# inout.net
KiCad netlist of a schematic drawn in Altium Designer
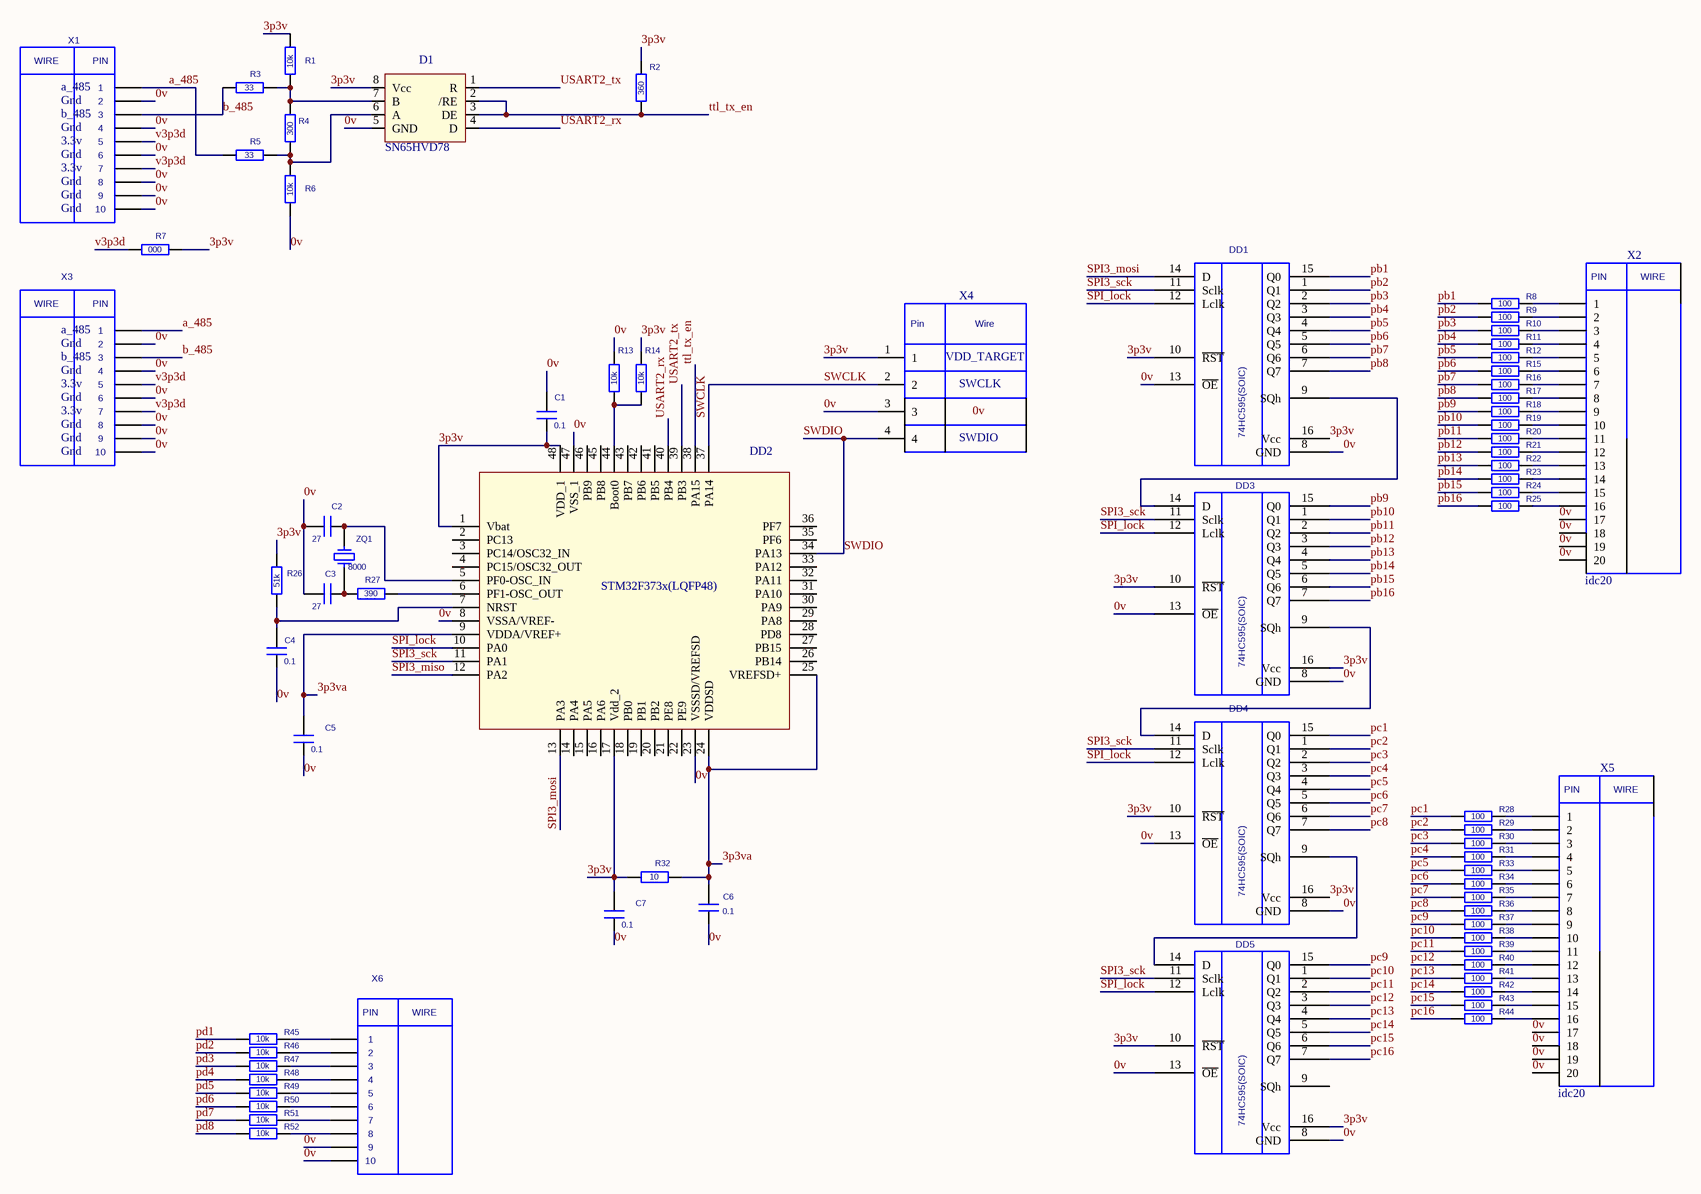
[diagram p0: inout.SchDoc]

(export (version "E")
  (design (tool "Eeschema 10.0.6"))
  (components
    (comp (ref "C1")
      (value "0.1")
      (footprint "CC0805")
      (description "CAP0805")
      (libsource (lib "alexsb") (part "CAP0805"))
    )
    (comp (ref "C2")
      (value "27")
      (footprint "CC0805")
      (description "CAP0805")
      (libsource (lib "alexsb") (part "CAP0805"))
    )
    (comp (ref "C3")
      (value "27")
      (footprint "CC0805")
      (description "CAP0805")
      (libsource (lib "alexsb") (part "CAP0805"))
    )
    (comp (ref "C4")
      (value "0.1")
      (footprint "CC0805")
      (description "CAP0805")
      (libsource (lib "alexsb") (part "CAP0805"))
    )
    (comp (ref "C5")
      (value "0.1")
      (footprint "CC0805")
      (description "CAP0805")
      (libsource (lib "alexsb") (part "CAP0805"))
    )
    (comp (ref "C6")
      (value "0.1")
      (footprint "CC0805")
      (description "CAP0805")
      (libsource (lib "alexsb") (part "CAP0805"))
    )
    (comp (ref "C7")
      (value "0.1")
      (footprint "CC0805")
      (description "CAP0805")
      (libsource (lib "alexsb") (part "CAP0805"))
    )
    (comp (ref "D1") (value "SN65HVD78") (footprint "8S1_M") (libsource (lib "as14120") (part "SN65HVD78")))
    (comp (ref "DD1")
      (value "74HC595(SOIC)")
      (footprint "SO16")
      (libsource (lib "alexsb") (part "74HC595(SOIC)"))
    )
    (comp (ref "DD2")
      (value "STM32F373x(LQFP48)")
      (footprint "LQFP48_L")
      (libsource (lib "alexsb") (part "STM32F373x(LQFP48)"))
    )
    (comp (ref "DD3")
      (value "74HC595(SOIC)")
      (footprint "SO16")
      (libsource (lib "alexsb") (part "74HC595(SOIC)"))
    )
    (comp (ref "DD4")
      (value "74HC595(SOIC)")
      (footprint "SO16")
      (libsource (lib "alexsb") (part "74HC595(SOIC)"))
    )
    (comp (ref "DD5")
      (value "74HC595(SOIC)")
      (footprint "SO16")
      (libsource (lib "alexsb") (part "74HC595(SOIC)"))
    )
    (comp (ref "R1")
      (value "10k")
      (footprint "RC0805")
      (description "RES0805")
      (fields (field (name "Comment") "1K 1% 0805(2012)"))
      (libsource (lib "") (part "RES0805_1"))
    )
    (comp (ref "R2")
      (value "360")
      (footprint "RC0805")
      (description "RES0805")
      (fields (field (name "Comment") "1K 1% 0805(2012)"))
      (libsource (lib "") (part "RES0805_1"))
    )
    (comp (ref "R3")
      (value "33")
      (footprint "RC0805")
      (description "RES0805")
      (fields (field (name "Comment") "1K 1% 0805(2012)"))
      (libsource (lib "") (part "RES0805_1"))
    )
    (comp (ref "R4")
      (value "300")
      (footprint "RC0805")
      (description "RES0805")
      (fields (field (name "Comment") "1K 1% 0805(2012)"))
      (libsource (lib "") (part "RES0805_1"))
    )
    (comp (ref "R5")
      (value "33")
      (footprint "RC0805")
      (description "RES0805")
      (fields (field (name "Comment") "1K 1% 0805(2012)"))
      (libsource (lib "") (part "RES0805_1"))
    )
    (comp (ref "R6")
      (value "10k")
      (footprint "RC0805")
      (description "RES0805")
      (fields (field (name "Comment") "1K 1% 0805(2012)"))
      (libsource (lib "") (part "RES0805_1"))
    )
    (comp (ref "R7")
      (value "000")
      (footprint "RC0805")
      (description "RES0805")
      (fields (field (name "Comment") "1K 1% 0805(2012)"))
      (libsource (lib "") (part "RES0805_1"))
    )
    (comp (ref "R8")
      (value "100")
      (footprint "RC0805")
      (description "RES0805")
      (fields (field (name "Comment") "1K 1% 0805(2012)"))
      (libsource (lib "alexsb") (part "RES0805"))
    )
    (comp (ref "R9")
      (value "100")
      (footprint "RC0805")
      (description "RES0805")
      (fields (field (name "Comment") "1K 1% 0805(2012)"))
      (libsource (lib "alexsb") (part "RES0805"))
    )
    (comp (ref "R10")
      (value "100")
      (footprint "RC0805")
      (description "RES0805")
      (fields (field (name "Comment") "1K 1% 0805(2012)"))
      (libsource (lib "alexsb") (part "RES0805"))
    )
    (comp (ref "R11")
      (value "100")
      (footprint "RC0805")
      (description "RES0805")
      (fields (field (name "Comment") "1K 1% 0805(2012)"))
      (libsource (lib "alexsb") (part "RES0805"))
    )
    (comp (ref "R12")
      (value "100")
      (footprint "RC0805")
      (description "RES0805")
      (fields (field (name "Comment") "1K 1% 0805(2012)"))
      (libsource (lib "alexsb") (part "RES0805"))
    )
    (comp (ref "R13")
      (value "10k")
      (footprint "RC0805")
      (description "RES0805")
      (libsource (lib "") (part "RES0805_1"))
    )
    (comp (ref "R14")
      (value "10k")
      (footprint "RC0805")
      (description "RES0805")
      (libsource (lib "") (part "RES0805_1"))
    )
    (comp (ref "R15")
      (value "100")
      (footprint "RC0805")
      (description "RES0805")
      (fields (field (name "Comment") "1K 1% 0805(2012)"))
      (libsource (lib "alexsb") (part "RES0805"))
    )
    (comp (ref "R16")
      (value "100")
      (footprint "RC0805")
      (description "RES0805")
      (fields (field (name "Comment") "1K 1% 0805(2012)"))
      (libsource (lib "alexsb") (part "RES0805"))
    )
    (comp (ref "R17")
      (value "100")
      (footprint "RC0805")
      (description "RES0805")
      (fields (field (name "Comment") "1K 1% 0805(2012)"))
      (libsource (lib "alexsb") (part "RES0805"))
    )
    (comp (ref "R18")
      (value "100")
      (footprint "RC0805")
      (description "RES0805")
      (fields (field (name "Comment") "1K 1% 0805(2012)"))
      (libsource (lib "alexsb") (part "RES0805"))
    )
    (comp (ref "R19")
      (value "100")
      (footprint "RC0805")
      (description "RES0805")
      (fields (field (name "Comment") "1K 1% 0805(2012)"))
      (libsource (lib "alexsb") (part "RES0805"))
    )
    (comp (ref "R20")
      (value "100")
      (footprint "RC0805")
      (description "RES0805")
      (fields (field (name "Comment") "1K 1% 0805(2012)"))
      (libsource (lib "alexsb") (part "RES0805"))
    )
    (comp (ref "R21")
      (value "100")
      (footprint "RC0805")
      (description "RES0805")
      (fields (field (name "Comment") "1K 1% 0805(2012)"))
      (libsource (lib "alexsb") (part "RES0805"))
    )
    (comp (ref "R22")
      (value "100")
      (footprint "RC0805")
      (description "RES0805")
      (fields (field (name "Comment") "1K 1% 0805(2012)"))
      (libsource (lib "alexsb") (part "RES0805"))
    )
    (comp (ref "R23")
      (value "100")
      (footprint "RC0805")
      (description "RES0805")
      (fields (field (name "Comment") "1K 1% 0805(2012)"))
      (libsource (lib "alexsb") (part "RES0805"))
    )
    (comp (ref "R24")
      (value "100")
      (footprint "RC0805")
      (description "RES0805")
      (fields (field (name "Comment") "1K 1% 0805(2012)"))
      (libsource (lib "alexsb") (part "RES0805"))
    )
    (comp (ref "R25")
      (value "100")
      (footprint "RC0805")
      (description "RES0805")
      (fields (field (name "Comment") "1K 1% 0805(2012)"))
      (libsource (lib "alexsb") (part "RES0805"))
    )
    (comp (ref "R26")
      (value "51k")
      (footprint "RC0805")
      (description "RES0805")
      (libsource (lib "") (part "RES0805_1"))
    )
    (comp (ref "R27")
      (value "390")
      (footprint "RC0805")
      (description "RES0805")
      (libsource (lib "") (part "RES0805_1"))
    )
    (comp (ref "R28")
      (value "100")
      (footprint "RC0805")
      (description "RES0805")
      (fields (field (name "Comment") "1K 1% 0805(2012)"))
      (libsource (lib "alexsb") (part "RES0805"))
    )
    (comp (ref "R29")
      (value "100")
      (footprint "RC0805")
      (description "RES0805")
      (fields (field (name "Comment") "1K 1% 0805(2012)"))
      (libsource (lib "alexsb") (part "RES0805"))
    )
    (comp (ref "R30")
      (value "100")
      (footprint "RC0805")
      (description "RES0805")
      (fields (field (name "Comment") "1K 1% 0805(2012)"))
      (libsource (lib "alexsb") (part "RES0805"))
    )
    (comp (ref "R31")
      (value "100")
      (footprint "RC0805")
      (description "RES0805")
      (fields (field (name "Comment") "1K 1% 0805(2012)"))
      (libsource (lib "alexsb") (part "RES0805"))
    )
    (comp (ref "R32")
      (value "10")
      (footprint "RC0805")
      (description "RES0805")
      (libsource (lib "alexsb") (part "RES0805"))
    )
    (comp (ref "R33")
      (value "100")
      (footprint "RC0805")
      (description "RES0805")
      (fields (field (name "Comment") "1K 1% 0805(2012)"))
      (libsource (lib "alexsb") (part "RES0805"))
    )
    (comp (ref "R34")
      (value "100")
      (footprint "RC0805")
      (description "RES0805")
      (fields (field (name "Comment") "1K 1% 0805(2012)"))
      (libsource (lib "alexsb") (part "RES0805"))
    )
    (comp (ref "R35")
      (value "100")
      (footprint "RC0805")
      (description "RES0805")
      (fields (field (name "Comment") "1K 1% 0805(2012)"))
      (libsource (lib "alexsb") (part "RES0805"))
    )
    (comp (ref "R36")
      (value "100")
      (footprint "RC0805")
      (description "RES0805")
      (fields (field (name "Comment") "1K 1% 0805(2012)"))
      (libsource (lib "alexsb") (part "RES0805"))
    )
    (comp (ref "R37")
      (value "100")
      (footprint "RC0805")
      (description "RES0805")
      (fields (field (name "Comment") "1K 1% 0805(2012)"))
      (libsource (lib "alexsb") (part "RES0805"))
    )
    (comp (ref "R38")
      (value "100")
      (footprint "RC0805")
      (description "RES0805")
      (fields (field (name "Comment") "1K 1% 0805(2012)"))
      (libsource (lib "alexsb") (part "RES0805"))
    )
    (comp (ref "R39")
      (value "100")
      (footprint "RC0805")
      (description "RES0805")
      (fields (field (name "Comment") "1K 1% 0805(2012)"))
      (libsource (lib "alexsb") (part "RES0805"))
    )
    (comp (ref "R40")
      (value "100")
      (footprint "RC0805")
      (description "RES0805")
      (fields (field (name "Comment") "1K 1% 0805(2012)"))
      (libsource (lib "alexsb") (part "RES0805"))
    )
    (comp (ref "R41")
      (value "100")
      (footprint "RC0805")
      (description "RES0805")
      (fields (field (name "Comment") "1K 1% 0805(2012)"))
      (libsource (lib "alexsb") (part "RES0805"))
    )
    (comp (ref "R42")
      (value "100")
      (footprint "RC0805")
      (description "RES0805")
      (fields (field (name "Comment") "1K 1% 0805(2012)"))
      (libsource (lib "alexsb") (part "RES0805"))
    )
    (comp (ref "R43")
      (value "100")
      (footprint "RC0805")
      (description "RES0805")
      (fields (field (name "Comment") "1K 1% 0805(2012)"))
      (libsource (lib "alexsb") (part "RES0805"))
    )
    (comp (ref "R44")
      (value "100")
      (footprint "RC0805")
      (description "RES0805")
      (fields (field (name "Comment") "1K 1% 0805(2012)"))
      (libsource (lib "alexsb") (part "RES0805"))
    )
    (comp (ref "R45")
      (value "10k")
      (footprint "RC0805")
      (description "RES0805")
      (fields (field (name "Comment") "1K 1% 0805(2012)"))
      (libsource (lib "alexsb") (part "RES0805"))
    )
    (comp (ref "R46")
      (value "10k")
      (footprint "RC0805")
      (description "RES0805")
      (fields (field (name "Comment") "1K 1% 0805(2012)"))
      (libsource (lib "alexsb") (part "RES0805"))
    )
    (comp (ref "R47")
      (value "10k")
      (footprint "RC0805")
      (description "RES0805")
      (fields (field (name "Comment") "1K 1% 0805(2012)"))
      (libsource (lib "alexsb") (part "RES0805"))
    )
    (comp (ref "R48")
      (value "10k")
      (footprint "RC0805")
      (description "RES0805")
      (fields (field (name "Comment") "1K 1% 0805(2012)"))
      (libsource (lib "alexsb") (part "RES0805"))
    )
    (comp (ref "R49")
      (value "10k")
      (footprint "RC0805")
      (description "RES0805")
      (fields (field (name "Comment") "1K 1% 0805(2012)"))
      (libsource (lib "alexsb") (part "RES0805"))
    )
    (comp (ref "R50")
      (value "10k")
      (footprint "RC0805")
      (description "RES0805")
      (fields (field (name "Comment") "1K 1% 0805(2012)"))
      (libsource (lib "alexsb") (part "RES0805"))
    )
    (comp (ref "R51")
      (value "10k")
      (footprint "RC0805")
      (description "RES0805")
      (fields (field (name "Comment") "1K 1% 0805(2012)"))
      (libsource (lib "alexsb") (part "RES0805"))
    )
    (comp (ref "R52")
      (value "10k")
      (footprint "RC0805")
      (description "RES0805")
      (fields (field (name "Comment") "1K 1% 0805(2012)"))
      (libsource (lib "alexsb") (part "RES0805"))
    )
    (comp (ref "X1") (value "IDC10") (footprint "IDC10M") (libsource (lib "alexsb") (part "IDC10")))
    (comp (ref "X2") (value "idc20") (footprint "IDC20M") (libsource (lib "alexsb") (part "idc20")))
    (comp (ref "X3") (value "IDC10") (footprint "IDC10M") (libsource (lib "alexsb") (part "IDC10")))
    (comp (ref "X4") (value "*") (footprint "4pin") (libsource (lib "*") (part "4pin")))
    (comp (ref "X5") (value "idc20") (footprint "IDC20M") (libsource (lib "alexsb") (part "idc20")))
    (comp (ref "X6") (value "IDC10") (footprint "IDC10M") (libsource (lib "alexsb") (part "IDC10")))
    (comp (ref "ZQ1")
      (value "8000")
      (footprint "CRYSTAL_Primary")
      (description "REZONATOR")
      (libsource (lib "alexsb") (part "REZONATOR"))
    )
  )
  (nets
    (net (code "1") (name "/0v") (class "Default")
      (node (ref "C1") (pin "2") (pintype "passive"))
      (node (ref "C2") (pin "2") (pintype "passive"))
      (node (ref "C3") (pin "2") (pintype "passive"))
      (node (ref "C4") (pin "1") (pintype "passive"))
      (node (ref "C5") (pin "1") (pintype "passive"))
      (node (ref "C6") (pin "1") (pintype "passive"))
      (node (ref "C7") (pin "1") (pintype "passive"))
      (node (ref "D1") (pin "5") (pinfunction "GND_5") (pintype "passive"))
      (node (ref "DD1") (pin "13") (pinfunction "~{OE}_13") (pintype "passive"))
      (node (ref "DD1") (pin "8") (pinfunction "GND_8") (pintype "passive"))
      (node (ref "DD2") (pin "23") (pinfunction "VSSSD/VREFSD_23") (pintype "passive"))
      (node (ref "DD2") (pin "47") (pinfunction "VSS_1_47") (pintype "passive"))
      (node (ref "DD2") (pin "8") (pinfunction "VSSA/VREF-_8") (pintype "passive"))
      (node (ref "DD3") (pin "13") (pinfunction "~{OE}_13") (pintype "passive"))
      (node (ref "DD3") (pin "8") (pinfunction "GND_8") (pintype "passive"))
      (node (ref "DD4") (pin "13") (pinfunction "~{OE}_13") (pintype "passive"))
      (node (ref "DD4") (pin "8") (pinfunction "GND_8") (pintype "passive"))
      (node (ref "DD5") (pin "13") (pinfunction "~{OE}_13") (pintype "passive"))
      (node (ref "DD5") (pin "8") (pinfunction "GND_8") (pintype "passive"))
      (node (ref "R13") (pin "2") (pintype "passive"))
      (node (ref "R6") (pin "2") (pintype "passive"))
      (node (ref "X1") (pin "10") (pintype "passive"))
      (node (ref "X1") (pin "2") (pintype "passive"))
      (node (ref "X1") (pin "4") (pintype "passive"))
      (node (ref "X1") (pin "6") (pintype "passive"))
      (node (ref "X1") (pin "8") (pintype "passive"))
      (node (ref "X1") (pin "9") (pintype "passive"))
      (node (ref "X2") (pin "17") (pinfunction "17_17") (pintype "passive"))
      (node (ref "X2") (pin "18") (pinfunction "18_18") (pintype "passive"))
      (node (ref "X2") (pin "19") (pinfunction "19_19") (pintype "passive"))
      (node (ref "X2") (pin "20") (pinfunction "20_20") (pintype "passive"))
      (node (ref "X3") (pin "10") (pintype "passive"))
      (node (ref "X3") (pin "2") (pintype "passive"))
      (node (ref "X3") (pin "4") (pintype "passive"))
      (node (ref "X3") (pin "6") (pintype "passive"))
      (node (ref "X3") (pin "8") (pintype "passive"))
      (node (ref "X3") (pin "9") (pintype "passive"))
      (node (ref "X4") (pin "3") (pinfunction "3_3") (pintype "passive"))
      (node (ref "X5") (pin "17") (pinfunction "17_17") (pintype "passive"))
      (node (ref "X5") (pin "18") (pinfunction "18_18") (pintype "passive"))
      (node (ref "X5") (pin "19") (pinfunction "19_19") (pintype "passive"))
      (node (ref "X5") (pin "20") (pinfunction "20_20") (pintype "passive"))
      (node (ref "X6") (pin "10") (pintype "passive"))
      (node (ref "X6") (pin "9") (pintype "passive"))
    )
    (net (code "2") (name "/3p3v") (class "Default")
      (node (ref "C1") (pin "1") (pintype "passive"))
      (node (ref "C7") (pin "2") (pintype "passive"))
      (node (ref "D1") (pin "8") (pinfunction "Vcc_8") (pintype "passive"))
      (node (ref "DD1") (pin "10") (pinfunction "~{RST}_10") (pintype "passive"))
      (node (ref "DD1") (pin "16") (pinfunction "Vcc_16") (pintype "passive"))
      (node (ref "DD2") (pin "1") (pinfunction "Vbat_1") (pintype "passive"))
      (node (ref "DD2") (pin "17") (pinfunction "Vdd_2_17") (pintype "passive"))
      (node (ref "DD2") (pin "48") (pinfunction "VDD_1_48") (pintype "passive"))
      (node (ref "DD3") (pin "10") (pinfunction "~{RST}_10") (pintype "passive"))
      (node (ref "DD3") (pin "16") (pinfunction "Vcc_16") (pintype "passive"))
      (node (ref "DD4") (pin "10") (pinfunction "~{RST}_10") (pintype "passive"))
      (node (ref "DD4") (pin "16") (pinfunction "Vcc_16") (pintype "passive"))
      (node (ref "DD5") (pin "10") (pinfunction "~{RST}_10") (pintype "passive"))
      (node (ref "DD5") (pin "16") (pinfunction "Vcc_16") (pintype "passive"))
      (node (ref "R1") (pin "1") (pintype "passive"))
      (node (ref "R14") (pin "2") (pintype "passive"))
      (node (ref "R2") (pin "1") (pintype "passive"))
      (node (ref "R26") (pin "2") (pintype "passive"))
      (node (ref "R32") (pin "1") (pintype "passive"))
      (node (ref "R7") (pin "2") (pintype "passive"))
      (node (ref "X4") (pin "1") (pinfunction "1_1") (pintype "passive"))
    )
    (net (code "3") (name "/3p3va") (class "Default")
      (node (ref "C5") (pin "2") (pintype "passive"))
      (node (ref "C6") (pin "2") (pintype "passive"))
      (node (ref "DD2") (pin "24") (pinfunction "VDDSD_24") (pintype "passive"))
      (node (ref "DD2") (pin "25") (pinfunction "VREFSD+_25") (pintype "passive"))
      (node (ref "DD2") (pin "9") (pinfunction "VDDA/VREF+_9") (pintype "passive"))
      (node (ref "R32") (pin "2") (pintype "passive"))
    )
    (net (code "4") (name "/SPI3_miso") (class "Default")
      (node (ref "DD2") (pin "12") (pinfunction "PA2_12") (pintype "passive"))
    )
    (net (code "5") (name "/SPI3_mosi") (class "Default")
      (node (ref "DD1") (pin "14") (pinfunction "D_14") (pintype "passive"))
      (node (ref "DD2") (pin "13") (pinfunction "PA3_13") (pintype "passive"))
    )
    (net (code "6") (name "/SPI3_sck") (class "Default")
      (node (ref "DD1") (pin "11") (pinfunction "Sclk_11") (pintype "passive"))
      (node (ref "DD2") (pin "11") (pinfunction "PA1_11") (pintype "passive"))
      (node (ref "DD3") (pin "11") (pinfunction "Sclk_11") (pintype "passive"))
      (node (ref "DD4") (pin "11") (pinfunction "Sclk_11") (pintype "passive"))
      (node (ref "DD5") (pin "11") (pinfunction "Sclk_11") (pintype "passive"))
    )
    (net (code "7") (name "/SPI_lock") (class "Default")
      (node (ref "DD1") (pin "12") (pinfunction "Lclk_12") (pintype "passive"))
      (node (ref "DD2") (pin "10") (pinfunction "PA0_10") (pintype "passive"))
      (node (ref "DD3") (pin "12") (pinfunction "Lclk_12") (pintype "passive"))
      (node (ref "DD4") (pin "12") (pinfunction "Lclk_12") (pintype "passive"))
      (node (ref "DD5") (pin "12") (pinfunction "Lclk_12") (pintype "passive"))
    )
    (net (code "8") (name "/SWCLK") (class "Default")
      (node (ref "DD2") (pin "37") (pinfunction "PA14_37") (pintype "passive"))
      (node (ref "X4") (pin "2") (pinfunction "2_2") (pintype "passive"))
    )
    (net (code "9") (name "/SWDIO") (class "Default")
      (node (ref "DD2") (pin "34") (pinfunction "PA13_34") (pintype "passive"))
      (node (ref "X4") (pin "4") (pinfunction "4_4") (pintype "passive"))
    )
    (net (code "10") (name "/USART2_rx") (class "Default")
      (node (ref "D1") (pin "4") (pinfunction "D_4") (pintype "passive"))
      (node (ref "DD2") (pin "40") (pinfunction "PB4_40") (pintype "passive"))
    )
    (net (code "11") (name "/USART2_tx") (class "Default")
      (node (ref "D1") (pin "1") (pinfunction "R_1") (pintype "passive"))
      (node (ref "DD2") (pin "39") (pinfunction "PB3_39") (pintype "passive"))
    )
    (net (code "12") (name "/a_485") (class "Default")
      (node (ref "R5") (pin "1") (pintype "passive"))
      (node (ref "X1") (pin "1") (pintype "passive"))
      (node (ref "X3") (pin "1") (pintype "passive"))
    )
    (net (code "13") (name "/b_485") (class "Default")
      (node (ref "R3") (pin "1") (pintype "passive"))
      (node (ref "X1") (pin "3") (pintype "passive"))
      (node (ref "X3") (pin "3") (pintype "passive"))
    )
    (net (code "14") (name "/pb1") (class "Default")
      (node (ref "DD1") (pin "15") (pinfunction "Q0_15") (pintype "passive"))
      (node (ref "R8") (pin "2") (pintype "passive"))
    )
    (net (code "15") (name "/pb2") (class "Default")
      (node (ref "DD1") (pin "1") (pinfunction "Q1_1") (pintype "passive"))
      (node (ref "R9") (pin "2") (pintype "passive"))
    )
    (net (code "16") (name "/pb3") (class "Default")
      (node (ref "DD1") (pin "2") (pinfunction "Q2_2") (pintype "passive"))
      (node (ref "R10") (pin "2") (pintype "passive"))
    )
    (net (code "17") (name "/pb4") (class "Default")
      (node (ref "DD1") (pin "3") (pinfunction "Q3_3") (pintype "passive"))
      (node (ref "R11") (pin "2") (pintype "passive"))
    )
    (net (code "18") (name "/pb5") (class "Default")
      (node (ref "DD1") (pin "4") (pinfunction "Q4_4") (pintype "passive"))
      (node (ref "R12") (pin "2") (pintype "passive"))
    )
    (net (code "19") (name "/pb6") (class "Default")
      (node (ref "DD1") (pin "5") (pinfunction "Q5_5") (pintype "passive"))
      (node (ref "R15") (pin "2") (pintype "passive"))
    )
    (net (code "20") (name "/pb7") (class "Default")
      (node (ref "DD1") (pin "6") (pinfunction "Q6_6") (pintype "passive"))
      (node (ref "R16") (pin "2") (pintype "passive"))
    )
    (net (code "21") (name "/pb8") (class "Default")
      (node (ref "DD1") (pin "7") (pinfunction "Q7_7") (pintype "passive"))
      (node (ref "R17") (pin "2") (pintype "passive"))
    )
    (net (code "22") (name "/pb9") (class "Default")
      (node (ref "DD3") (pin "15") (pinfunction "Q0_15") (pintype "passive"))
      (node (ref "R18") (pin "2") (pintype "passive"))
    )
    (net (code "23") (name "/pb10") (class "Default")
      (node (ref "DD3") (pin "1") (pinfunction "Q1_1") (pintype "passive"))
      (node (ref "R19") (pin "2") (pintype "passive"))
    )
    (net (code "24") (name "/pb11") (class "Default")
      (node (ref "DD3") (pin "2") (pinfunction "Q2_2") (pintype "passive"))
      (node (ref "R20") (pin "2") (pintype "passive"))
    )
    (net (code "25") (name "/pb12") (class "Default")
      (node (ref "DD3") (pin "3") (pinfunction "Q3_3") (pintype "passive"))
      (node (ref "R21") (pin "2") (pintype "passive"))
    )
    (net (code "26") (name "/pb13") (class "Default")
      (node (ref "DD3") (pin "4") (pinfunction "Q4_4") (pintype "passive"))
      (node (ref "R22") (pin "2") (pintype "passive"))
    )
    (net (code "27") (name "/pb14") (class "Default")
      (node (ref "DD3") (pin "5") (pinfunction "Q5_5") (pintype "passive"))
      (node (ref "R23") (pin "2") (pintype "passive"))
    )
    (net (code "28") (name "/pb15") (class "Default")
      (node (ref "DD3") (pin "6") (pinfunction "Q6_6") (pintype "passive"))
      (node (ref "R24") (pin "2") (pintype "passive"))
    )
    (net (code "29") (name "/pb16") (class "Default")
      (node (ref "DD3") (pin "7") (pinfunction "Q7_7") (pintype "passive"))
      (node (ref "R25") (pin "2") (pintype "passive"))
    )
    (net (code "30") (name "/pc1") (class "Default")
      (node (ref "DD4") (pin "15") (pinfunction "Q0_15") (pintype "passive"))
      (node (ref "R28") (pin "2") (pintype "passive"))
    )
    (net (code "31") (name "/pc2") (class "Default")
      (node (ref "DD4") (pin "1") (pinfunction "Q1_1") (pintype "passive"))
      (node (ref "R29") (pin "2") (pintype "passive"))
    )
    (net (code "32") (name "/pc3") (class "Default")
      (node (ref "DD4") (pin "2") (pinfunction "Q2_2") (pintype "passive"))
      (node (ref "R30") (pin "2") (pintype "passive"))
    )
    (net (code "33") (name "/pc4") (class "Default")
      (node (ref "DD4") (pin "3") (pinfunction "Q3_3") (pintype "passive"))
      (node (ref "R31") (pin "2") (pintype "passive"))
    )
    (net (code "34") (name "/pc5") (class "Default")
      (node (ref "DD4") (pin "4") (pinfunction "Q4_4") (pintype "passive"))
      (node (ref "R33") (pin "2") (pintype "passive"))
    )
    (net (code "35") (name "/pc6") (class "Default")
      (node (ref "DD4") (pin "5") (pinfunction "Q5_5") (pintype "passive"))
      (node (ref "R34") (pin "2") (pintype "passive"))
    )
    (net (code "36") (name "/pc7") (class "Default")
      (node (ref "DD4") (pin "6") (pinfunction "Q6_6") (pintype "passive"))
      (node (ref "R35") (pin "2") (pintype "passive"))
    )
    (net (code "37") (name "/pc8") (class "Default")
      (node (ref "DD4") (pin "7") (pinfunction "Q7_7") (pintype "passive"))
      (node (ref "R36") (pin "2") (pintype "passive"))
    )
    (net (code "38") (name "/pc9") (class "Default")
      (node (ref "DD5") (pin "15") (pinfunction "Q0_15") (pintype "passive"))
      (node (ref "R37") (pin "2") (pintype "passive"))
    )
    (net (code "39") (name "/pc10") (class "Default")
      (node (ref "DD5") (pin "1") (pinfunction "Q1_1") (pintype "passive"))
      (node (ref "R38") (pin "2") (pintype "passive"))
    )
    (net (code "40") (name "/pc11") (class "Default")
      (node (ref "DD5") (pin "2") (pinfunction "Q2_2") (pintype "passive"))
      (node (ref "R39") (pin "2") (pintype "passive"))
    )
    (net (code "41") (name "/pc12") (class "Default")
      (node (ref "DD5") (pin "3") (pinfunction "Q3_3") (pintype "passive"))
      (node (ref "R40") (pin "2") (pintype "passive"))
    )
    (net (code "42") (name "/pc13") (class "Default")
      (node (ref "DD5") (pin "4") (pinfunction "Q4_4") (pintype "passive"))
      (node (ref "R41") (pin "2") (pintype "passive"))
    )
    (net (code "43") (name "/pc14") (class "Default")
      (node (ref "DD5") (pin "5") (pinfunction "Q5_5") (pintype "passive"))
      (node (ref "R42") (pin "2") (pintype "passive"))
    )
    (net (code "44") (name "/pc15") (class "Default")
      (node (ref "DD5") (pin "6") (pinfunction "Q6_6") (pintype "passive"))
      (node (ref "R43") (pin "2") (pintype "passive"))
    )
    (net (code "45") (name "/pc16") (class "Default")
      (node (ref "DD5") (pin "7") (pinfunction "Q7_7") (pintype "passive"))
      (node (ref "R44") (pin "2") (pintype "passive"))
    )
    (net (code "46") (name "/pd1") (class "Default") (node (ref "R45") (pin "2") (pintype "passive")))
    (net (code "47") (name "/pd2") (class "Default") (node (ref "R46") (pin "2") (pintype "passive")))
    (net (code "48") (name "/pd3") (class "Default") (node (ref "R47") (pin "2") (pintype "passive")))
    (net (code "49") (name "/pd4") (class "Default") (node (ref "R48") (pin "2") (pintype "passive")))
    (net (code "50") (name "/pd5") (class "Default") (node (ref "R49") (pin "2") (pintype "passive")))
    (net (code "51") (name "/pd6") (class "Default") (node (ref "R50") (pin "2") (pintype "passive")))
    (net (code "52") (name "/pd7") (class "Default") (node (ref "R51") (pin "2") (pintype "passive")))
    (net (code "53") (name "/pd8") (class "Default") (node (ref "R52") (pin "2") (pintype "passive")))
    (net (code "54") (name "/ttl_tx_en") (class "Default")
      (node (ref "D1") (pin "2") (pinfunction "/RE_2") (pintype "passive"))
      (node (ref "D1") (pin "3") (pinfunction "DE_3") (pintype "passive"))
      (node (ref "DD2") (pin "38") (pinfunction "PA15_38") (pintype "passive"))
      (node (ref "R2") (pin "2") (pintype "passive"))
    )
    (net (code "55") (name "/v3p3d") (class "Default")
      (node (ref "R7") (pin "1") (pintype "passive"))
      (node (ref "X1") (pin "5") (pintype "passive"))
      (node (ref "X1") (pin "7") (pintype "passive"))
      (node (ref "X3") (pin "5") (pintype "passive"))
      (node (ref "X3") (pin "7") (pintype "passive"))
    )
    (net (code "56") (name "Net-(C3-Pad1)") (class "Default")
      (node (ref "C3") (pin "1") (pintype "passive"))
      (node (ref "R27") (pin "2") (pintype "passive"))
      (node (ref "ZQ1") (pin "1") (pintype "passive"))
    )
    (net (code "57") (name "Net-(D1-A)") (class "Default")
      (node (ref "D1") (pin "6") (pinfunction "A_6") (pintype "passive"))
      (node (ref "R4") (pin "2") (pintype "passive"))
      (node (ref "R5") (pin "2") (pintype "passive"))
      (node (ref "R6") (pin "1") (pintype "passive"))
    )
    (net (code "58") (name "Net-(D1-B)") (class "Default")
      (node (ref "D1") (pin "7") (pinfunction "B_7") (pintype "passive"))
      (node (ref "R1") (pin "2") (pintype "passive"))
      (node (ref "R3") (pin "2") (pintype "passive"))
      (node (ref "R4") (pin "1") (pintype "passive"))
    )
    (net (code "59") (name "Net-(DD1-SQh)") (class "Default")
      (node (ref "DD1") (pin "9") (pinfunction "SQh_9") (pintype "passive"))
      (node (ref "DD3") (pin "14") (pinfunction "D_14") (pintype "passive"))
    )
    (net (code "60") (name "Net-(DD2-Boot0)") (class "Default")
      (node (ref "DD2") (pin "44") (pinfunction "Boot0_44") (pintype "passive"))
      (node (ref "R13") (pin "1") (pintype "passive"))
      (node (ref "R14") (pin "1") (pintype "passive"))
    )
    (net (code "61") (name "Net-(DD2-NRST)") (class "Default")
      (node (ref "C4") (pin "2") (pintype "passive"))
      (node (ref "DD2") (pin "7") (pinfunction "NRST_7") (pintype "passive"))
      (node (ref "R26") (pin "1") (pintype "passive"))
    )
    (net (code "62") (name "Net-(DD2-PF0-OSC_IN)") (class "Default")
      (node (ref "C2") (pin "1") (pintype "passive"))
      (node (ref "DD2") (pin "5") (pinfunction "PF0-OSC_IN_5") (pintype "passive"))
      (node (ref "ZQ1") (pin "2") (pintype "passive"))
    )
    (net (code "63") (name "Net-(DD2-PF1-OSC_OUT)") (class "Default")
      (node (ref "DD2") (pin "6") (pinfunction "PF1-OSC_OUT_6") (pintype "passive"))
      (node (ref "R27") (pin "1") (pintype "passive"))
    )
    (net (code "64") (name "Net-(DD3-SQh)") (class "Default")
      (node (ref "DD3") (pin "9") (pinfunction "SQh_9") (pintype "passive"))
      (node (ref "DD4") (pin "14") (pinfunction "D_14") (pintype "passive"))
    )
    (net (code "65") (name "Net-(DD4-SQh)") (class "Default")
      (node (ref "DD4") (pin "9") (pinfunction "SQh_9") (pintype "passive"))
      (node (ref "DD5") (pin "14") (pinfunction "D_14") (pintype "passive"))
    )
    (net (code "66") (name "Net-(R8-Pad1)") (class "Default")
      (node (ref "R8") (pin "1") (pintype "passive"))
      (node (ref "X2") (pin "1") (pinfunction "1_1") (pintype "passive"))
    )
    (net (code "67") (name "Net-(R9-Pad1)") (class "Default")
      (node (ref "R9") (pin "1") (pintype "passive"))
      (node (ref "X2") (pin "2") (pinfunction "2_2") (pintype "passive"))
    )
    (net (code "68") (name "Net-(R10-Pad1)") (class "Default")
      (node (ref "R10") (pin "1") (pintype "passive"))
      (node (ref "X2") (pin "3") (pinfunction "3_3") (pintype "passive"))
    )
    (net (code "69") (name "Net-(R11-Pad1)") (class "Default")
      (node (ref "R11") (pin "1") (pintype "passive"))
      (node (ref "X2") (pin "4") (pinfunction "4_4") (pintype "passive"))
    )
    (net (code "70") (name "Net-(R12-Pad1)") (class "Default")
      (node (ref "R12") (pin "1") (pintype "passive"))
      (node (ref "X2") (pin "5") (pinfunction "5_5") (pintype "passive"))
    )
    (net (code "71") (name "Net-(R15-Pad1)") (class "Default")
      (node (ref "R15") (pin "1") (pintype "passive"))
      (node (ref "X2") (pin "6") (pinfunction "6_6") (pintype "passive"))
    )
    (net (code "72") (name "Net-(R16-Pad1)") (class "Default")
      (node (ref "R16") (pin "1") (pintype "passive"))
      (node (ref "X2") (pin "7") (pinfunction "7_7") (pintype "passive"))
    )
    (net (code "73") (name "Net-(R17-Pad1)") (class "Default")
      (node (ref "R17") (pin "1") (pintype "passive"))
      (node (ref "X2") (pin "8") (pinfunction "8_8") (pintype "passive"))
    )
    (net (code "74") (name "Net-(R18-Pad1)") (class "Default")
      (node (ref "R18") (pin "1") (pintype "passive"))
      (node (ref "X2") (pin "9") (pinfunction "9_9") (pintype "passive"))
    )
    (net (code "75") (name "Net-(R19-Pad1)") (class "Default")
      (node (ref "R19") (pin "1") (pintype "passive"))
      (node (ref "X2") (pin "10") (pinfunction "10_10") (pintype "passive"))
    )
    (net (code "76") (name "Net-(R20-Pad1)") (class "Default")
      (node (ref "R20") (pin "1") (pintype "passive"))
      (node (ref "X2") (pin "11") (pinfunction "11_11") (pintype "passive"))
    )
    (net (code "77") (name "Net-(R21-Pad1)") (class "Default")
      (node (ref "R21") (pin "1") (pintype "passive"))
      (node (ref "X2") (pin "12") (pinfunction "12_12") (pintype "passive"))
    )
    (net (code "78") (name "Net-(R22-Pad1)") (class "Default")
      (node (ref "R22") (pin "1") (pintype "passive"))
      (node (ref "X2") (pin "13") (pinfunction "13_13") (pintype "passive"))
    )
    (net (code "79") (name "Net-(R23-Pad1)") (class "Default")
      (node (ref "R23") (pin "1") (pintype "passive"))
      (node (ref "X2") (pin "14") (pinfunction "14_14") (pintype "passive"))
    )
    (net (code "80") (name "Net-(R24-Pad1)") (class "Default")
      (node (ref "R24") (pin "1") (pintype "passive"))
      (node (ref "X2") (pin "15") (pinfunction "15_15") (pintype "passive"))
    )
    (net (code "81") (name "Net-(R25-Pad1)") (class "Default")
      (node (ref "R25") (pin "1") (pintype "passive"))
      (node (ref "X2") (pin "16") (pinfunction "16_16") (pintype "passive"))
    )
    (net (code "82") (name "Net-(R28-Pad1)") (class "Default")
      (node (ref "R28") (pin "1") (pintype "passive"))
      (node (ref "X5") (pin "1") (pinfunction "1_1") (pintype "passive"))
    )
    (net (code "83") (name "Net-(R29-Pad1)") (class "Default")
      (node (ref "R29") (pin "1") (pintype "passive"))
      (node (ref "X5") (pin "2") (pinfunction "2_2") (pintype "passive"))
    )
    (net (code "84") (name "Net-(R30-Pad1)") (class "Default")
      (node (ref "R30") (pin "1") (pintype "passive"))
      (node (ref "X5") (pin "3") (pinfunction "3_3") (pintype "passive"))
    )
    (net (code "85") (name "Net-(R31-Pad1)") (class "Default")
      (node (ref "R31") (pin "1") (pintype "passive"))
      (node (ref "X5") (pin "4") (pinfunction "4_4") (pintype "passive"))
    )
    (net (code "86") (name "Net-(R33-Pad1)") (class "Default")
      (node (ref "R33") (pin "1") (pintype "passive"))
      (node (ref "X5") (pin "5") (pinfunction "5_5") (pintype "passive"))
    )
    (net (code "87") (name "Net-(R34-Pad1)") (class "Default")
      (node (ref "R34") (pin "1") (pintype "passive"))
      (node (ref "X5") (pin "6") (pinfunction "6_6") (pintype "passive"))
    )
    (net (code "88") (name "Net-(R35-Pad1)") (class "Default")
      (node (ref "R35") (pin "1") (pintype "passive"))
      (node (ref "X5") (pin "7") (pinfunction "7_7") (pintype "passive"))
    )
    (net (code "89") (name "Net-(R36-Pad1)") (class "Default")
      (node (ref "R36") (pin "1") (pintype "passive"))
      (node (ref "X5") (pin "8") (pinfunction "8_8") (pintype "passive"))
    )
    (net (code "90") (name "Net-(R37-Pad1)") (class "Default")
      (node (ref "R37") (pin "1") (pintype "passive"))
      (node (ref "X5") (pin "9") (pinfunction "9_9") (pintype "passive"))
    )
    (net (code "91") (name "Net-(R38-Pad1)") (class "Default")
      (node (ref "R38") (pin "1") (pintype "passive"))
      (node (ref "X5") (pin "10") (pinfunction "10_10") (pintype "passive"))
    )
    (net (code "92") (name "Net-(R39-Pad1)") (class "Default")
      (node (ref "R39") (pin "1") (pintype "passive"))
      (node (ref "X5") (pin "11") (pinfunction "11_11") (pintype "passive"))
    )
    (net (code "93") (name "Net-(R40-Pad1)") (class "Default")
      (node (ref "R40") (pin "1") (pintype "passive"))
      (node (ref "X5") (pin "12") (pinfunction "12_12") (pintype "passive"))
    )
    (net (code "94") (name "Net-(R41-Pad1)") (class "Default")
      (node (ref "R41") (pin "1") (pintype "passive"))
      (node (ref "X5") (pin "13") (pinfunction "13_13") (pintype "passive"))
    )
    (net (code "95") (name "Net-(R42-Pad1)") (class "Default")
      (node (ref "R42") (pin "1") (pintype "passive"))
      (node (ref "X5") (pin "14") (pinfunction "14_14") (pintype "passive"))
    )
    (net (code "96") (name "Net-(R43-Pad1)") (class "Default")
      (node (ref "R43") (pin "1") (pintype "passive"))
      (node (ref "X5") (pin "15") (pinfunction "15_15") (pintype "passive"))
    )
    (net (code "97") (name "Net-(R44-Pad1)") (class "Default")
      (node (ref "R44") (pin "1") (pintype "passive"))
      (node (ref "X5") (pin "16") (pinfunction "16_16") (pintype "passive"))
    )
    (net (code "98") (name "Net-(R45-Pad1)") (class "Default")
      (node (ref "R45") (pin "1") (pintype "passive"))
      (node (ref "X6") (pin "1") (pintype "passive"))
    )
    (net (code "99") (name "Net-(R46-Pad1)") (class "Default")
      (node (ref "R46") (pin "1") (pintype "passive"))
      (node (ref "X6") (pin "2") (pintype "passive"))
    )
    (net (code "100") (name "Net-(R47-Pad1)") (class "Default")
      (node (ref "R47") (pin "1") (pintype "passive"))
      (node (ref "X6") (pin "3") (pintype "passive"))
    )
    (net (code "101") (name "Net-(R48-Pad1)") (class "Default")
      (node (ref "R48") (pin "1") (pintype "passive"))
      (node (ref "X6") (pin "4") (pintype "passive"))
    )
    (net (code "102") (name "Net-(R49-Pad1)") (class "Default")
      (node (ref "R49") (pin "1") (pintype "passive"))
      (node (ref "X6") (pin "5") (pintype "passive"))
    )
    (net (code "103") (name "Net-(R50-Pad1)") (class "Default")
      (node (ref "R50") (pin "1") (pintype "passive"))
      (node (ref "X6") (pin "6") (pintype "passive"))
    )
    (net (code "104") (name "Net-(R51-Pad1)") (class "Default")
      (node (ref "R51") (pin "1") (pintype "passive"))
      (node (ref "X6") (pin "7") (pintype "passive"))
    )
    (net (code "105") (name "Net-(R52-Pad1)") (class "Default")
      (node (ref "R52") (pin "1") (pintype "passive"))
      (node (ref "X6") (pin "8") (pintype "passive"))
    )
    (net (code "106") (name "unconnected-(DD2-PA4-Pad14)") (class "Default")
      (node (ref "DD2") (pin "14") (pinfunction "PA4_14") (pintype "passive"))
    )
    (net (code "107") (name "unconnected-(DD2-PA5-Pad15)") (class "Default")
      (node (ref "DD2") (pin "15") (pinfunction "PA5_15") (pintype "passive"))
    )
    (net (code "108") (name "unconnected-(DD2-PA6-Pad16)") (class "Default")
      (node (ref "DD2") (pin "16") (pinfunction "PA6_16") (pintype "passive"))
    )
    (net (code "109") (name "unconnected-(DD2-PA8-Pad29)") (class "Default")
      (node (ref "DD2") (pin "29") (pinfunction "PA8_29") (pintype "passive"))
    )
    (net (code "110") (name "unconnected-(DD2-PA9-Pad30)") (class "Default")
      (node (ref "DD2") (pin "30") (pinfunction "PA9_30") (pintype "passive"))
    )
    (net (code "111") (name "unconnected-(DD2-PA10-Pad31)") (class "Default")
      (node (ref "DD2") (pin "31") (pinfunction "PA10_31") (pintype "passive"))
    )
    (net (code "112") (name "unconnected-(DD2-PA11-Pad32)") (class "Default")
      (node (ref "DD2") (pin "32") (pinfunction "PA11_32") (pintype "passive"))
    )
    (net (code "113") (name "unconnected-(DD2-PA12-Pad33)") (class "Default")
      (node (ref "DD2") (pin "33") (pinfunction "PA12_33") (pintype "passive"))
    )
    (net (code "114") (name "unconnected-(DD2-PB0-Pad18)") (class "Default")
      (node (ref "DD2") (pin "18") (pinfunction "PB0_18") (pintype "passive"))
    )
    (net (code "115") (name "unconnected-(DD2-PB1-Pad19)") (class "Default")
      (node (ref "DD2") (pin "19") (pinfunction "PB1_19") (pintype "passive"))
    )
    (net (code "116") (name "unconnected-(DD2-PB2-Pad20)") (class "Default")
      (node (ref "DD2") (pin "20") (pinfunction "PB2_20") (pintype "passive"))
    )
    (net (code "117") (name "unconnected-(DD2-PB5-Pad41)") (class "Default")
      (node (ref "DD2") (pin "41") (pinfunction "PB5_41") (pintype "passive"))
    )
    (net (code "118") (name "unconnected-(DD2-PB6-Pad42)") (class "Default")
      (node (ref "DD2") (pin "42") (pinfunction "PB6_42") (pintype "passive"))
    )
    (net (code "119") (name "unconnected-(DD2-PB7-Pad43)") (class "Default")
      (node (ref "DD2") (pin "43") (pinfunction "PB7_43") (pintype "passive"))
    )
    (net (code "120") (name "unconnected-(DD2-PB8-Pad45)") (class "Default")
      (node (ref "DD2") (pin "45") (pinfunction "PB8_45") (pintype "passive"))
    )
    (net (code "121") (name "unconnected-(DD2-PB9-Pad46)") (class "Default")
      (node (ref "DD2") (pin "46") (pinfunction "PB9_46") (pintype "passive"))
    )
    (net (code "122") (name "unconnected-(DD2-PB14-Pad26)") (class "Default")
      (node (ref "DD2") (pin "26") (pinfunction "PB14_26") (pintype "passive"))
    )
    (net (code "123") (name "unconnected-(DD2-PB15-Pad27)") (class "Default")
      (node (ref "DD2") (pin "27") (pinfunction "PB15_27") (pintype "passive"))
    )
    (net (code "124") (name "unconnected-(DD2-PC13-Pad2)") (class "Default")
      (node (ref "DD2") (pin "2") (pinfunction "PC13_2") (pintype "passive"))
    )
    (net (code "125") (name "unconnected-(DD2-PC14{slash}OSC32_IN-Pad3)") (class "Default")
      (node (ref "DD2") (pin "3") (pinfunction "PC14/OSC32_IN_3") (pintype "passive"))
    )
    (net (code "126") (name "unconnected-(DD2-PC15{slash}OSC32_OUT-Pad4)") (class "Default")
      (node (ref "DD2") (pin "4") (pinfunction "PC15/OSC32_OUT_4") (pintype "passive"))
    )
    (net (code "127") (name "unconnected-(DD2-PD8-Pad28)") (class "Default")
      (node (ref "DD2") (pin "28") (pinfunction "PD8_28") (pintype "passive"))
    )
    (net (code "128") (name "unconnected-(DD2-PE8-Pad21)") (class "Default")
      (node (ref "DD2") (pin "21") (pinfunction "PE8_21") (pintype "passive"))
    )
    (net (code "129") (name "unconnected-(DD2-PE9-Pad22)") (class "Default")
      (node (ref "DD2") (pin "22") (pinfunction "PE9_22") (pintype "passive"))
    )
    (net (code "130") (name "unconnected-(DD2-PF6-Pad35)") (class "Default")
      (node (ref "DD2") (pin "35") (pinfunction "PF6_35") (pintype "passive"))
    )
    (net (code "131") (name "unconnected-(DD2-PF7-Pad36)") (class "Default")
      (node (ref "DD2") (pin "36") (pinfunction "PF7_36") (pintype "passive"))
    )
    (net (code "132") (name "unconnected-(DD5-SQh-Pad9)") (class "Default")
      (node (ref "DD5") (pin "9") (pinfunction "SQh_9") (pintype "passive"))
    )
  )
)
